# PDM-S06-V00-CAN.net
KiCad netlist of a schematic drawn in Altium Designer
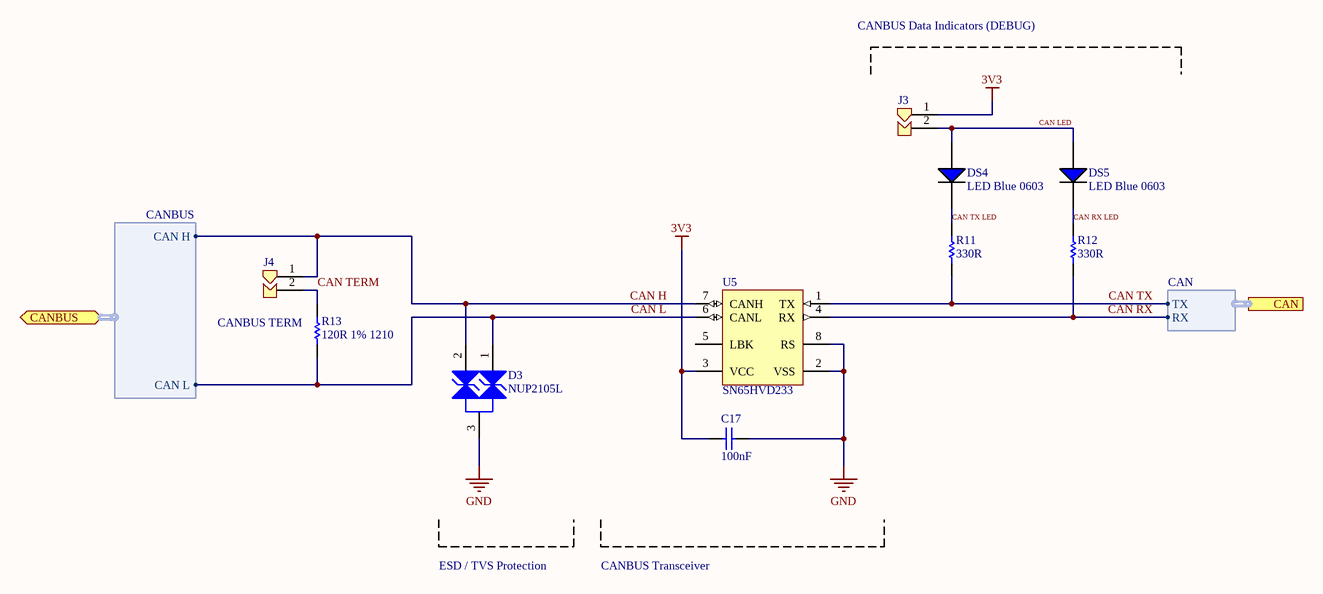
[diagram p0: PDM-S06-V00-CAN.SchDoc]

(export (version "E")
  (design (tool "Eeschema 10.0.6"))
  (components
    (comp (ref "C17")
      (value "100nF")
      (footprint "Cap_Ceramic_0603")
      (description "Capacitor, Ceramic, SMD, 100nF, 50V, 5%, X7R, 0603")
      (libsource (lib "StandardCapacitors") (part "100nF 50V 5% X7R 0603"))
    )
    (comp (ref "D3")
      (value "NUP2105L")
      (footprint "NUP2105L")
      (libsource (lib "QUTMS_CANLibrary") (part "NUP2105L"))
    )
    (comp (ref "DS4")
      (value "LED Blue 0603")
      (footprint "LED BLUE 0603")
      (libsource (lib "QUTMS_LEDLibrary") (part "LED BLUE 0603"))
    )
    (comp (ref "DS5")
      (value "LED Blue 0603")
      (footprint "LED BLUE 0603")
      (libsource (lib "QUTMS_LEDLibrary") (part "LED BLUE 0603"))
    )
    (comp (ref "J3")
      (value "Jumper 2Way Solderable")
      (footprint "Jumper_2Way_Solderable")
      (description "Jumper 2Way Side Solderable")
      (libsource (lib "QUTMS_JumperLibrary") (part "Jumper 2Way Side Solderable"))
    )
    (comp (ref "J4")
      (value "Jumper 2Way Solderable")
      (footprint "Jumper_2Way_Solderable")
      (description "Jumper 2Way Side Solderable")
      (libsource (lib "QUTMS_JumperLibrary") (part "Jumper 2Way Side Solderable"))
    )
    (comp (ref "R11")
      (value "330R")
      (footprint "Res_ThinFilm_0603")
      (description "Resistor, SMD, 330R, 0.1W, 5%, 0603")
      (libsource (lib "StandardResistors") (part "330R 5% 0603"))
    )
    (comp (ref "R12")
      (value "330R")
      (footprint "Res_ThinFilm_0603")
      (description "Resistor, SMD, 330R, 0.1W, 5%, 0603")
      (libsource (lib "StandardResistors") (part "330R 5% 0603"))
    )
    (comp (ref "R13")
      (value "120R 1% 1210")
      (footprint "Res_ThinFilm_1210")
      (description "Resistor, SMD, 120R, 0.25W, 1%, 1210")
      (libsource (lib "StandardResistors") (part "120R 1% 1210"))
    )
    (comp (ref "U5")
      (value "SN65HVD233")
      (footprint "SN65HVD233DR")
      (libsource (lib "QUTMS_CANLibrary") (part "SN65HVD233"))
    )
  )
  (nets
    (net (code "3") (name "/CAN H") (class "Default")
      (node (ref "D3") (pin "2") (pinfunction "2_2") (pintype "passive"))
      (node (ref "J4") (pin "1") (pinfunction "1_1") (pintype "passive"))
      (node (ref "U5") (pin "7") (pinfunction "CANH_7") (pintype "bidirectional"))
    )
    (net (code "4") (name "/CAN L") (class "Default")
      (node (ref "D3") (pin "1") (pinfunction "1_1") (pintype "passive"))
      (node (ref "R13") (pin "1") (pinfunction "1_1") (pintype "passive"))
      (node (ref "U5") (pin "6") (pinfunction "CANL_6") (pintype "bidirectional"))
    )
    (net (code "5") (name "/CAN LED") (class "Default")
      (node (ref "DS4") (pin "1") (pinfunction "A_1") (pintype "passive"))
      (node (ref "DS5") (pin "1") (pinfunction "A_1") (pintype "passive"))
      (node (ref "J3") (pin "2") (pinfunction "2_2") (pintype "passive"))
    )
    (net (code "6") (name "/CAN RX") (class "Default")
      (node (ref "R12") (pin "1") (pinfunction "1_1") (pintype "passive"))
      (node (ref "U5") (pin "4") (pinfunction "RX_4") (pintype "output"))
    )
    (net (code "7") (name "/CAN RX LED") (class "Default")
      (node (ref "DS5") (pin "2") (pinfunction "C_2") (pintype "passive"))
      (node (ref "R12") (pin "2") (pinfunction "2_2") (pintype "passive"))
    )
    (net (code "8") (name "/CAN TERM") (class "Default")
      (node (ref "J4") (pin "2") (pinfunction "2_2") (pintype "passive"))
      (node (ref "R13") (pin "2") (pinfunction "2_2") (pintype "passive"))
    )
    (net (code "9") (name "/CAN TX") (class "Default")
      (node (ref "R11") (pin "1") (pinfunction "1_1") (pintype "passive"))
      (node (ref "U5") (pin "1") (pinfunction "TX_1") (pintype "input"))
    )
    (net (code "10") (name "/CAN TX LED") (class "Default")
      (node (ref "DS4") (pin "2") (pinfunction "C_2") (pintype "passive"))
      (node (ref "R11") (pin "2") (pinfunction "2_2") (pintype "passive"))
    )
    (net (code "13") (name "3V3") (class "Default")
      (node (ref "C17") (pin "2") (pinfunction "2_2") (pintype "passive"))
      (node (ref "J3") (pin "1") (pinfunction "1_1") (pintype "passive"))
      (node (ref "U5") (pin "3") (pinfunction "VCC_3") (pintype "passive"))
    )
    (net (code "14") (name "GND") (class "Default")
      (node (ref "C17") (pin "1") (pinfunction "1_1") (pintype "passive"))
      (node (ref "D3") (pin "3") (pinfunction "3_3") (pintype "passive"))
      (node (ref "U5") (pin "2") (pinfunction "VSS_2") (pintype "passive"))
      (node (ref "U5") (pin "8") (pinfunction "RS_8") (pintype "passive"))
    )
    (net (code "15") (name "unconnected-(U5-LBK-Pad5)") (class "Default")
      (node (ref "U5") (pin "5") (pinfunction "LBK_5") (pintype "passive"))
    )
  )
)
